# LineOut_Headphone_Rev2.net
KiCad netlist of a schematic drawn in EAGLE
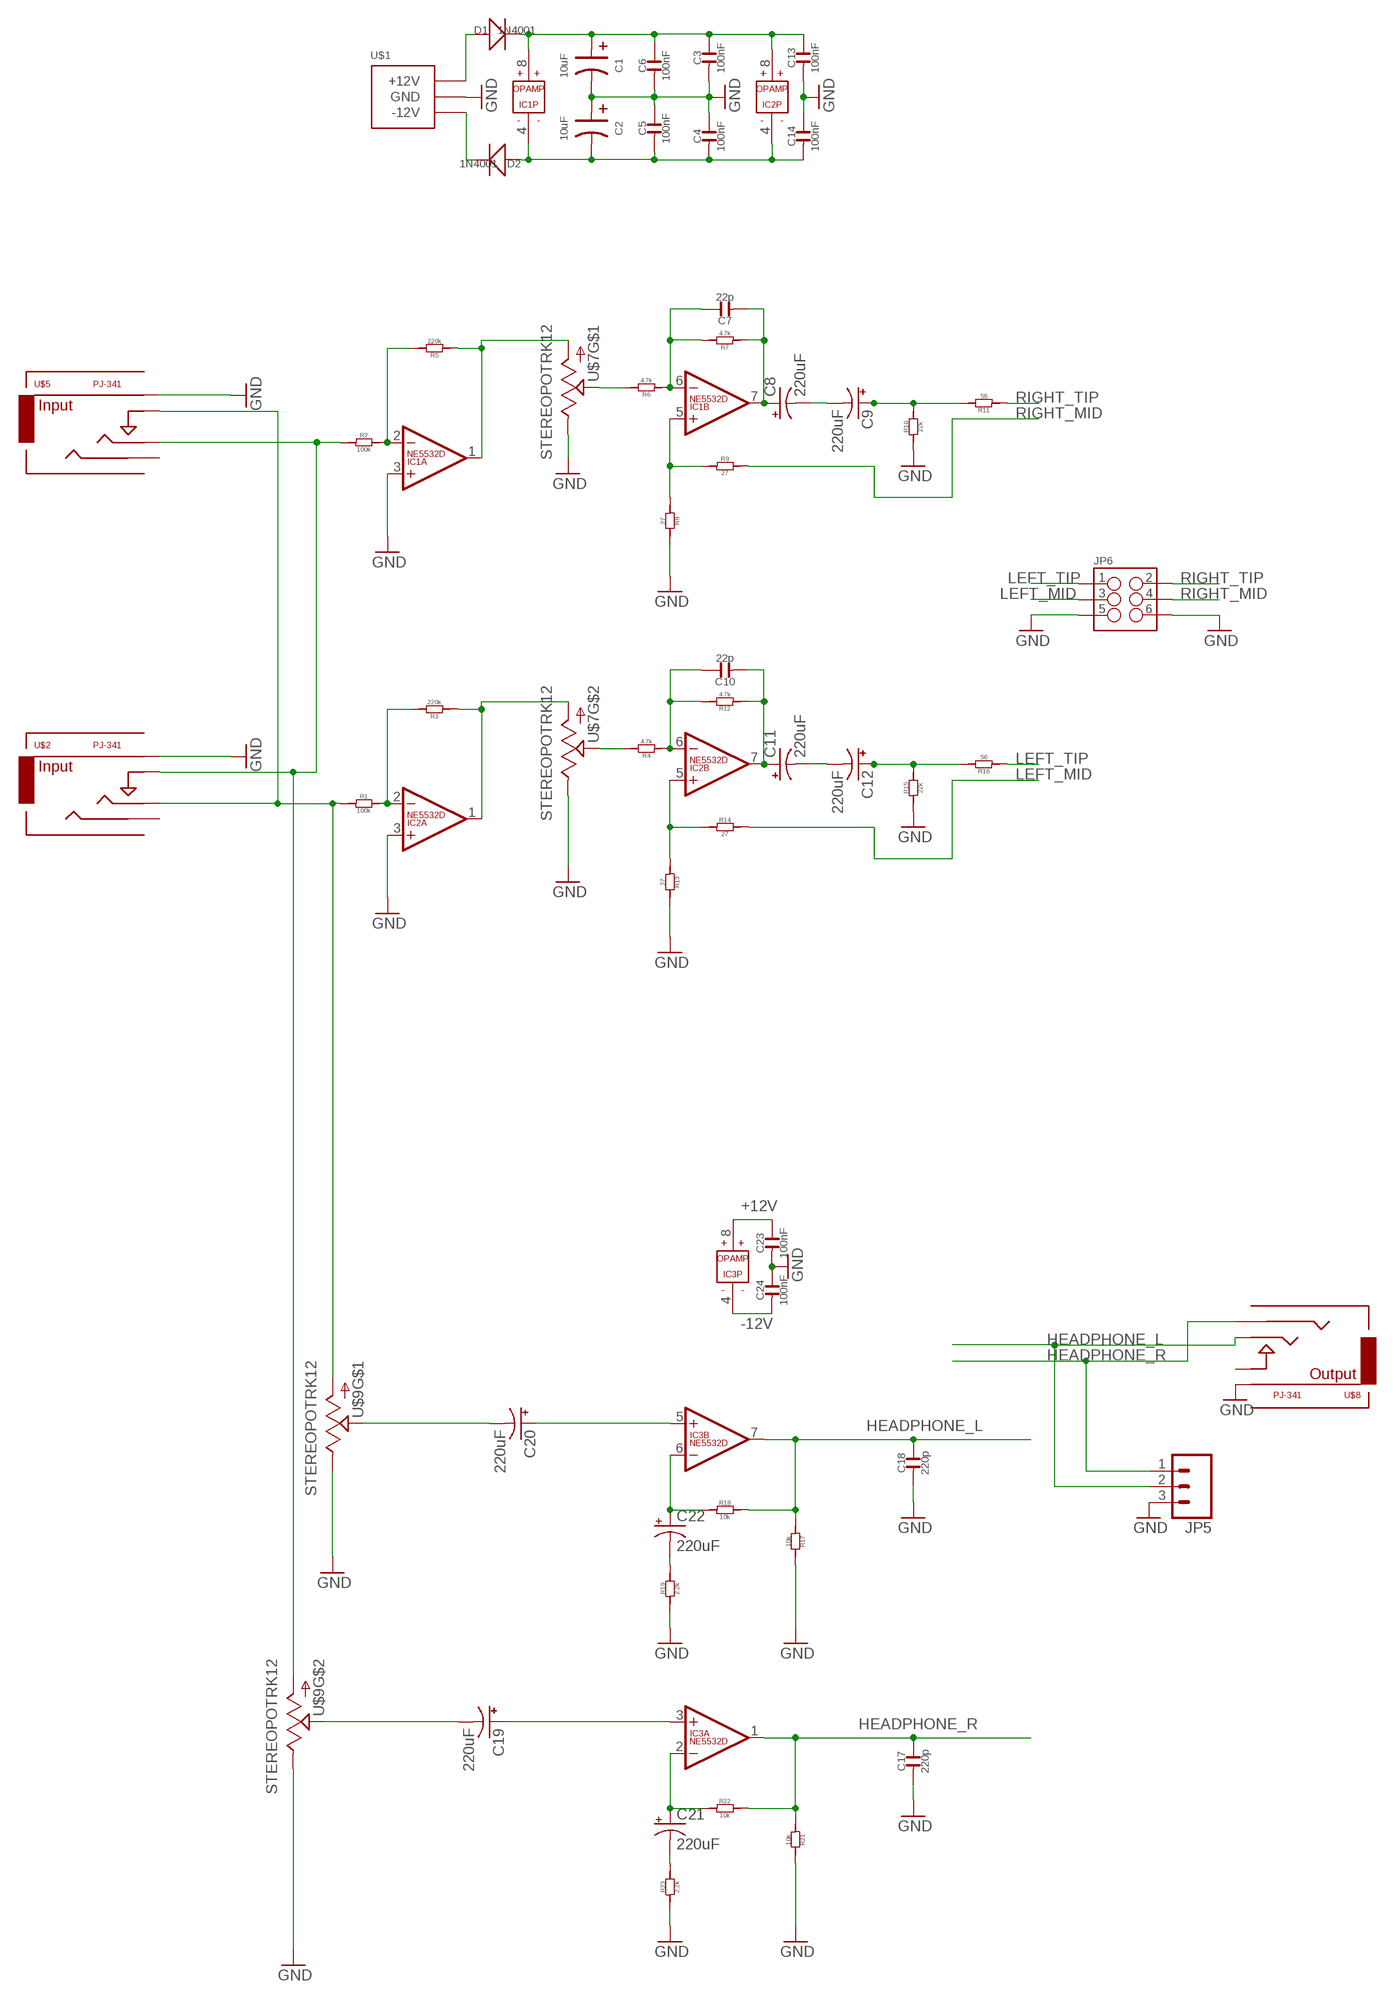
[diagram p0: schematic, sheet 1]

(export (version "E")
  (design (tool "Eeschema 10.0.6"))
  (components
    (comp (ref "C1")
      (value "10uF")
      (footprint "eagle-import:CASE-A_3216")
      (libsource (lib "eagle-import") (part "C-POLAR-A"))
    )
    (comp (ref "C2")
      (value "10uF")
      (footprint "eagle-import:CASE-A_3216")
      (libsource (lib "eagle-import") (part "C-POLAR-A"))
    )
    (comp (ref "C3")
      (value "100nF")
      (footprint "eagle-import:C0603")
      (libsource (lib "eagle-import") (part "C-0603"))
    )
    (comp (ref "C4")
      (value "100nF")
      (footprint "eagle-import:C0603")
      (libsource (lib "eagle-import") (part "C-0603"))
    )
    (comp (ref "C5")
      (value "100nF")
      (footprint "eagle-import:C0603")
      (libsource (lib "eagle-import") (part "C-0603"))
    )
    (comp (ref "C6")
      (value "100nF")
      (footprint "eagle-import:C0603")
      (libsource (lib "eagle-import") (part "C-0603"))
    )
    (comp (ref "C7")
      (value "22p")
      (footprint "eagle-import:C0603")
      (libsource (lib "eagle-import") (part "C-0603"))
    )
    (comp (ref "C8")
      (value "220uF")
      (footprint "eagle-import:153CLV-0505")
      (libsource (lib "eagle-import") (part "CPOL-US153CLV-0505"))
    )
    (comp (ref "C9")
      (value "220uF")
      (footprint "eagle-import:153CLV-0505")
      (libsource (lib "eagle-import") (part "CPOL-US153CLV-0505"))
    )
    (comp (ref "C10")
      (value "22p")
      (footprint "eagle-import:C0603")
      (libsource (lib "eagle-import") (part "C-0603"))
    )
    (comp (ref "C11")
      (value "220uF")
      (footprint "eagle-import:153CLV-0505")
      (libsource (lib "eagle-import") (part "CPOL-US153CLV-0505"))
    )
    (comp (ref "C12")
      (value "220uF")
      (footprint "eagle-import:153CLV-0505")
      (libsource (lib "eagle-import") (part "CPOL-US153CLV-0505"))
    )
    (comp (ref "C13")
      (value "100nF")
      (footprint "eagle-import:C0603")
      (libsource (lib "eagle-import") (part "C-0603"))
    )
    (comp (ref "C14")
      (value "100nF")
      (footprint "eagle-import:C0603")
      (libsource (lib "eagle-import") (part "C-0603"))
    )
    (comp (ref "C17")
      (value "220p")
      (footprint "eagle-import:C0603")
      (libsource (lib "eagle-import") (part "C-0603"))
    )
    (comp (ref "C18")
      (value "220p")
      (footprint "eagle-import:C0603")
      (libsource (lib "eagle-import") (part "C-0603"))
    )
    (comp (ref "C19")
      (value "220uF")
      (footprint "eagle-import:153CLV-0505")
      (libsource (lib "eagle-import") (part "CPOL-US153CLV-0505"))
    )
    (comp (ref "C20")
      (value "220uF")
      (footprint "eagle-import:153CLV-0505")
      (libsource (lib "eagle-import") (part "CPOL-US153CLV-0505"))
    )
    (comp (ref "C21")
      (value "220uF")
      (footprint "eagle-import:153CLV-0505")
      (libsource (lib "eagle-import") (part "CPOL-US153CLV-0505"))
    )
    (comp (ref "C22")
      (value "220uF")
      (footprint "eagle-import:153CLV-0505")
      (libsource (lib "eagle-import") (part "CPOL-US153CLV-0505"))
    )
    (comp (ref "C23")
      (value "100nF")
      (footprint "eagle-import:C0603")
      (libsource (lib "eagle-import") (part "C-0603"))
    )
    (comp (ref "C24")
      (value "100nF")
      (footprint "eagle-import:C0603")
      (libsource (lib "eagle-import") (part "C-0603"))
    )
    (comp (ref "D1")
      (value "1N4001")
      (footprint "eagle-import:SOD123")
      (libsource (lib "eagle-import") (part "D-SOD-123"))
    )
    (comp (ref "D2")
      (value "1N4001")
      (footprint "eagle-import:SOD123")
      (libsource (lib "eagle-import") (part "D-SOD-123"))
    )
    (comp (ref "IC1")
      (value "NE5532D")
      (footprint "eagle-import:SO08")
      (libsource (lib "eagle-import") (part "NE5532D"))
    )
    (comp (ref "IC2")
      (value "NE5532D")
      (footprint "eagle-import:SO08")
      (libsource (lib "eagle-import") (part "NE5532D"))
    )
    (comp (ref "IC3")
      (value "NE5532D")
      (footprint "eagle-import:SO08")
      (libsource (lib "eagle-import") (part "NE5532D"))
    )
    (comp (ref "JP5")
      (value "M03PTH")
      (footprint "eagle-import:1X03")
      (libsource (lib "eagle-import") (part "M03PTH"))
    )
    (comp (ref "JP6")
      (value "M03X2")
      (footprint "eagle-import:2X3-SHROUDED")
      (libsource (lib "eagle-import") (part "M03X2"))
    )
    (comp (ref "R1")
      (value "100k")
      (footprint "eagle-import:R0603")
      (libsource (lib "eagle-import") (part "R-0603"))
    )
    (comp (ref "R2")
      (value "100k")
      (footprint "eagle-import:R0603")
      (libsource (lib "eagle-import") (part "R-0603"))
    )
    (comp (ref "R3")
      (value "220k")
      (footprint "eagle-import:R0603")
      (libsource (lib "eagle-import") (part "R-0603"))
    )
    (comp (ref "R4")
      (value "4.7k")
      (footprint "eagle-import:R0603")
      (libsource (lib "eagle-import") (part "R-0603"))
    )
    (comp (ref "R5")
      (value "220k")
      (footprint "eagle-import:R0603")
      (libsource (lib "eagle-import") (part "R-0603"))
    )
    (comp (ref "R6")
      (value "4.7k")
      (footprint "eagle-import:R0603")
      (libsource (lib "eagle-import") (part "R-0603"))
    )
    (comp (ref "R7")
      (value "4.7k")
      (footprint "eagle-import:R0603")
      (libsource (lib "eagle-import") (part "R-0603"))
    )
    (comp (ref "R8")
      (value "27")
      (footprint "eagle-import:R0603")
      (libsource (lib "eagle-import") (part "R-0603"))
    )
    (comp (ref "R9")
      (value "27")
      (footprint "eagle-import:R0603")
      (libsource (lib "eagle-import") (part "R-0603"))
    )
    (comp (ref "R10")
      (value "22k")
      (footprint "eagle-import:R0603")
      (libsource (lib "eagle-import") (part "R-0603"))
    )
    (comp (ref "R11")
      (value "56")
      (footprint "eagle-import:R0603")
      (libsource (lib "eagle-import") (part "R-0603"))
    )
    (comp (ref "R12")
      (value "4.7k")
      (footprint "eagle-import:R0603")
      (libsource (lib "eagle-import") (part "R-0603"))
    )
    (comp (ref "R13")
      (value "27")
      (footprint "eagle-import:R0603")
      (libsource (lib "eagle-import") (part "R-0603"))
    )
    (comp (ref "R14")
      (value "27")
      (footprint "eagle-import:R0603")
      (libsource (lib "eagle-import") (part "R-0603"))
    )
    (comp (ref "R15")
      (value "22k")
      (footprint "eagle-import:R0603")
      (libsource (lib "eagle-import") (part "R-0603"))
    )
    (comp (ref "R16")
      (value "56")
      (footprint "eagle-import:R0603")
      (libsource (lib "eagle-import") (part "R-0603"))
    )
    (comp (ref "R17")
      (value "10k")
      (footprint "eagle-import:R0603")
      (libsource (lib "eagle-import") (part "R-0603"))
    )
    (comp (ref "R18")
      (value "10k")
      (footprint "eagle-import:R0603")
      (libsource (lib "eagle-import") (part "R-0603"))
    )
    (comp (ref "R19")
      (value "2.2k")
      (footprint "eagle-import:R0603")
      (libsource (lib "eagle-import") (part "R-0603"))
    )
    (comp (ref "R21")
      (value "10k")
      (footprint "eagle-import:R0603")
      (libsource (lib "eagle-import") (part "R-0603"))
    )
    (comp (ref "R22")
      (value "10k")
      (footprint "eagle-import:R0603")
      (libsource (lib "eagle-import") (part "R-0603"))
    )
    (comp (ref "R23")
      (value "2.2k")
      (footprint "eagle-import:R0603")
      (libsource (lib "eagle-import") (part "R-0603"))
    )
    (comp (ref "U$1")
      (value "POWER_SIMPLE10")
      (footprint "eagle-import:POWER_10")
      (libsource (lib "eagle-import") (part "POWER_SIMPLE10"))
    )
    (comp (ref "U$2")
      (value "PJ-341")
      (footprint "eagle-import:3.5MM-JACK-SWITCH-13MM-INPUT")
      (libsource (lib "eagle-import") (part "AUDIO-JACKINPUT"))
    )
    (comp (ref "U$5")
      (value "PJ-341")
      (footprint "eagle-import:3.5MM-JACK-SWITCH-13MM-INPUT")
      (libsource (lib "eagle-import") (part "AUDIO-JACKINPUT"))
    )
    (comp (ref "U$7")
      (value "STEREOPOTRK12")
      (footprint "eagle-import:RK12")
      (libsource (lib "eagle-import") (part "STEREOPOTRK12"))
    )
    (comp (ref "U$8")
      (value "PJ-341")
      (footprint "eagle-import:3.5MM-JACK-SWITCH-13MM-OUTPUT")
      (libsource (lib "eagle-import") (part "AUDIO-JACKOUTPUT"))
    )
    (comp (ref "U$9")
      (value "STEREOPOTRK12")
      (footprint "eagle-import:RK12")
      (libsource (lib "eagle-import") (part "STEREOPOTRK12"))
    )
  )
  (nets
    (net (code "1") (name "/+12V") (class "Default")
      (node (ref "C1") (pin "+") (pinfunction "1_+") (pintype "bidirectional"))
      (node (ref "C13") (pin "2") (pinfunction "2_2") (pintype "bidirectional"))
      (node (ref "C23") (pin "2") (pinfunction "2_2") (pintype "bidirectional"))
      (node (ref "C3") (pin "2") (pinfunction "2_2") (pintype "bidirectional"))
      (node (ref "C6") (pin "2") (pinfunction "2_2") (pintype "bidirectional"))
      (node (ref "D1") (pin "-") (pinfunction "-_-") (pintype "passive"))
      (node (ref "IC1") (pin "8") (pinfunction "V+_8") (pintype "power_in"))
      (node (ref "IC2") (pin "8") (pinfunction "V+_8") (pintype "power_in"))
      (node (ref "IC3") (pin "8") (pinfunction "V+_8") (pintype "power_in"))
    )
    (net (code "2") (name "/-12V") (class "Default")
      (node (ref "C14") (pin "1") (pinfunction "1_1") (pintype "bidirectional"))
      (node (ref "C2") (pin "-") (pinfunction "2_-") (pintype "bidirectional"))
      (node (ref "C24") (pin "1") (pinfunction "1_1") (pintype "bidirectional"))
      (node (ref "C4") (pin "1") (pinfunction "1_1") (pintype "bidirectional"))
      (node (ref "C5") (pin "1") (pinfunction "1_1") (pintype "bidirectional"))
      (node (ref "D2") (pin "+") (pinfunction "+_+") (pintype "passive"))
      (node (ref "IC1") (pin "4") (pinfunction "V-_4") (pintype "power_in"))
      (node (ref "IC2") (pin "4") (pinfunction "V-_4") (pintype "power_in"))
      (node (ref "IC3") (pin "4") (pinfunction "V-_4") (pintype "power_in"))
    )
    (net (code "3") (name "/HEADPHONE_L") (class "Default")
      (node (ref "C18") (pin "2") (pinfunction "2_2") (pintype "bidirectional"))
      (node (ref "IC3") (pin "7") (pinfunction "OUT_7") (pintype "output"))
      (node (ref "JP5") (pin "2") (pinfunction "2_2") (pintype "passive"))
      (node (ref "R17") (pin "1") (pinfunction "1_1") (pintype "bidirectional"))
      (node (ref "R18") (pin "2") (pinfunction "2_2") (pintype "bidirectional"))
      (node (ref "U$8") (pin "TIP@3") (pinfunction "TIP_TIP@3") (pintype "bidirectional"))
    )
    (net (code "4") (name "/HEADPHONE_R") (class "Default")
      (node (ref "C17") (pin "2") (pinfunction "2_2") (pintype "bidirectional"))
      (node (ref "IC3") (pin "1") (pinfunction "OUT_1") (pintype "output"))
      (node (ref "JP5") (pin "1") (pinfunction "1_1") (pintype "passive"))
      (node (ref "R21") (pin "1") (pinfunction "1_1") (pintype "bidirectional"))
      (node (ref "R22") (pin "2") (pinfunction "2_2") (pintype "bidirectional"))
      (node (ref "U$8") (pin "SECOND@3") (pinfunction "SECOND_SECOND@3") (pintype "bidirectional"))
    )
    (net (code "5") (name "/LEFT_MID") (class "Default")
      (node (ref "JP6") (pin "3") (pinfunction "3_3") (pintype "bidirectional"))
      (node (ref "R14") (pin "2") (pinfunction "2_2") (pintype "bidirectional"))
    )
    (net (code "6") (name "/LEFT_TIP") (class "Default")
      (node (ref "JP6") (pin "1") (pinfunction "1_1") (pintype "bidirectional"))
      (node (ref "R16") (pin "1") (pinfunction "1_1") (pintype "bidirectional"))
    )
    (net (code "7") (name "/RIGHT_MID") (class "Default")
      (node (ref "JP6") (pin "4") (pinfunction "4_4") (pintype "bidirectional"))
      (node (ref "R9") (pin "2") (pinfunction "2_2") (pintype "bidirectional"))
    )
    (net (code "8") (name "/RIGHT_TIP") (class "Default")
      (node (ref "JP6") (pin "2") (pinfunction "2_2") (pintype "bidirectional"))
      (node (ref "R11") (pin "1") (pinfunction "1_1") (pintype "bidirectional"))
    )
    (net (code "9") (name "GND") (class "Default")
      (node (ref "C1") (pin "-") (pinfunction "2_-") (pintype "bidirectional"))
      (node (ref "C13") (pin "1") (pinfunction "1_1") (pintype "bidirectional"))
      (node (ref "C14") (pin "2") (pinfunction "2_2") (pintype "bidirectional"))
      (node (ref "C17") (pin "1") (pinfunction "1_1") (pintype "bidirectional"))
      (node (ref "C18") (pin "1") (pinfunction "1_1") (pintype "bidirectional"))
      (node (ref "C2") (pin "+") (pinfunction "1_+") (pintype "bidirectional"))
      (node (ref "C23") (pin "1") (pinfunction "1_1") (pintype "bidirectional"))
      (node (ref "C24") (pin "2") (pinfunction "2_2") (pintype "bidirectional"))
      (node (ref "C3") (pin "1") (pinfunction "1_1") (pintype "bidirectional"))
      (node (ref "C4") (pin "2") (pinfunction "2_2") (pintype "bidirectional"))
      (node (ref "C5") (pin "2") (pinfunction "2_2") (pintype "bidirectional"))
      (node (ref "C6") (pin "1") (pinfunction "1_1") (pintype "bidirectional"))
      (node (ref "IC1") (pin "3") (pinfunction "+IN_3") (pintype "input"))
      (node (ref "IC2") (pin "3") (pinfunction "+IN_3") (pintype "input"))
      (node (ref "JP5") (pin "3") (pinfunction "3_3") (pintype "passive"))
      (node (ref "JP6") (pin "5") (pinfunction "5_5") (pintype "bidirectional"))
      (node (ref "JP6") (pin "6") (pinfunction "6_6") (pintype "bidirectional"))
      (node (ref "R10") (pin "1") (pinfunction "1_1") (pintype "bidirectional"))
      (node (ref "R13") (pin "2") (pinfunction "2_2") (pintype "bidirectional"))
      (node (ref "R15") (pin "1") (pinfunction "1_1") (pintype "bidirectional"))
      (node (ref "R17") (pin "2") (pinfunction "2_2") (pintype "bidirectional"))
      (node (ref "R19") (pin "1") (pinfunction "1_1") (pintype "bidirectional"))
      (node (ref "R21") (pin "2") (pinfunction "2_2") (pintype "bidirectional"))
      (node (ref "R23") (pin "1") (pinfunction "1_1") (pintype "bidirectional"))
      (node (ref "R8") (pin "2") (pinfunction "2_2") (pintype "bidirectional"))
      (node (ref "U$1") (pin "3") (pinfunction "GND_3") (pintype "bidirectional"))
      (node (ref "U$1") (pin "4") (pinfunction "GND_4") (pintype "bidirectional"))
      (node (ref "U$1") (pin "5") (pinfunction "GND_5") (pintype "bidirectional"))
      (node (ref "U$1") (pin "6") (pinfunction "GND_6") (pintype "bidirectional"))
      (node (ref "U$1") (pin "7") (pinfunction "GND_7") (pintype "bidirectional"))
      (node (ref "U$1") (pin "8") (pinfunction "GND_8") (pintype "bidirectional"))
      (node (ref "U$2") (pin "RING@3") (pinfunction "RING_RING@3") (pintype "bidirectional"))
      (node (ref "U$5") (pin "RING@3") (pinfunction "RING_RING@3") (pintype "bidirectional"))
      (node (ref "U$7") (pin "R1_1") (pinfunction "E_R1_1") (pintype "passive"))
      (node (ref "U$7") (pin "R2_1") (pinfunction "E_R2_1") (pintype "passive"))
      (node (ref "U$8") (pin "RING@3") (pinfunction "RING_RING@3") (pintype "bidirectional"))
      (node (ref "U$9") (pin "R1_1") (pinfunction "E_R1_1") (pintype "passive"))
      (node (ref "U$9") (pin "R2_1") (pinfunction "E_R2_1") (pintype "passive"))
    )
    (net (code "10") (name "Net-(C8-Pad-)") (class "Default")
      (node (ref "C8") (pin "-") (pinfunction "-_-") (pintype "passive"))
      (node (ref "C9") (pin "-") (pinfunction "-_-") (pintype "passive"))
    )
    (net (code "11") (name "Net-(C9-Pad+)") (class "Default")
      (node (ref "C9") (pin "+") (pinfunction "+_+") (pintype "passive"))
      (node (ref "R10") (pin "2") (pinfunction "2_2") (pintype "bidirectional"))
      (node (ref "R11") (pin "2") (pinfunction "2_2") (pintype "bidirectional"))
    )
    (net (code "12") (name "Net-(C11-Pad-)") (class "Default")
      (node (ref "C11") (pin "-") (pinfunction "-_-") (pintype "passive"))
      (node (ref "C12") (pin "-") (pinfunction "-_-") (pintype "passive"))
    )
    (net (code "13") (name "Net-(C12-Pad+)") (class "Default")
      (node (ref "C12") (pin "+") (pinfunction "+_+") (pintype "passive"))
      (node (ref "R15") (pin "2") (pinfunction "2_2") (pintype "bidirectional"))
      (node (ref "R16") (pin "2") (pinfunction "2_2") (pintype "bidirectional"))
    )
    (net (code "14") (name "Net-(C21-Pad-)") (class "Default")
      (node (ref "C21") (pin "-") (pinfunction "-_-") (pintype "passive"))
      (node (ref "R23") (pin "2") (pinfunction "2_2") (pintype "bidirectional"))
    )
    (net (code "15") (name "Net-(C22-Pad-)") (class "Default")
      (node (ref "C22") (pin "-") (pinfunction "-_-") (pintype "passive"))
      (node (ref "R19") (pin "2") (pinfunction "2_2") (pintype "bidirectional"))
    )
    (net (code "16") (name "Net-(D1-Pad+)") (class "Default")
      (node (ref "D1") (pin "+") (pinfunction "+_+") (pintype "passive"))
      (node (ref "U$1") (pin "10") (pinfunction "+12V_10") (pintype "bidirectional"))
      (node (ref "U$1") (pin "9") (pinfunction "+12V_9") (pintype "bidirectional"))
    )
    (net (code "17") (name "Net-(D2-Pad-)") (class "Default")
      (node (ref "D2") (pin "-") (pinfunction "-_-") (pintype "passive"))
      (node (ref "U$1") (pin "1") (pinfunction "-12V_1") (pintype "bidirectional"))
      (node (ref "U$1") (pin "2") (pinfunction "-12V_2") (pintype "bidirectional"))
    )
    (net (code "18") (name "Net-(IC1A--IN)") (class "Default")
      (node (ref "IC1") (pin "2") (pinfunction "-IN_2") (pintype "input"))
      (node (ref "R2") (pin "2") (pinfunction "2_2") (pintype "bidirectional"))
      (node (ref "R5") (pin "2") (pinfunction "2_2") (pintype "bidirectional"))
    )
    (net (code "19") (name "Net-(IC1A-OUT)") (class "Default")
      (node (ref "IC1") (pin "1") (pinfunction "OUT_1") (pintype "output"))
      (node (ref "R5") (pin "1") (pinfunction "1_1") (pintype "bidirectional"))
      (node (ref "U$7") (pin "R1_3") (pinfunction "A_R1_3") (pintype "passive"))
    )
    (net (code "20") (name "Net-(IC1B-+IN)") (class "Default")
      (node (ref "IC1") (pin "5") (pinfunction "+IN_5") (pintype "input"))
      (node (ref "R8") (pin "1") (pinfunction "1_1") (pintype "bidirectional"))
      (node (ref "R9") (pin "1") (pinfunction "1_1") (pintype "bidirectional"))
    )
    (net (code "21") (name "Net-(IC1B--IN)") (class "Default")
      (node (ref "C7") (pin "2") (pinfunction "2_2") (pintype "bidirectional"))
      (node (ref "IC1") (pin "6") (pinfunction "-IN_6") (pintype "input"))
      (node (ref "R6") (pin "1") (pinfunction "1_1") (pintype "bidirectional"))
      (node (ref "R7") (pin "2") (pinfunction "2_2") (pintype "bidirectional"))
    )
    (net (code "22") (name "Net-(IC1B-OUT)") (class "Default")
      (node (ref "C7") (pin "1") (pinfunction "1_1") (pintype "bidirectional"))
      (node (ref "C8") (pin "+") (pinfunction "+_+") (pintype "passive"))
      (node (ref "IC1") (pin "7") (pinfunction "OUT_7") (pintype "output"))
      (node (ref "R7") (pin "1") (pinfunction "1_1") (pintype "bidirectional"))
    )
    (net (code "23") (name "Net-(IC2A--IN)") (class "Default")
      (node (ref "IC2") (pin "2") (pinfunction "-IN_2") (pintype "input"))
      (node (ref "R1") (pin "2") (pinfunction "2_2") (pintype "bidirectional"))
      (node (ref "R3") (pin "2") (pinfunction "2_2") (pintype "bidirectional"))
    )
    (net (code "24") (name "Net-(IC2A-OUT)") (class "Default")
      (node (ref "IC2") (pin "1") (pinfunction "OUT_1") (pintype "output"))
      (node (ref "R3") (pin "1") (pinfunction "1_1") (pintype "bidirectional"))
      (node (ref "U$7") (pin "R2_3") (pinfunction "A_R2_3") (pintype "passive"))
    )
    (net (code "25") (name "Net-(IC2B-+IN)") (class "Default")
      (node (ref "IC2") (pin "5") (pinfunction "+IN_5") (pintype "input"))
      (node (ref "R13") (pin "1") (pinfunction "1_1") (pintype "bidirectional"))
      (node (ref "R14") (pin "1") (pinfunction "1_1") (pintype "bidirectional"))
    )
    (net (code "26") (name "Net-(IC2B--IN)") (class "Default")
      (node (ref "C10") (pin "2") (pinfunction "2_2") (pintype "bidirectional"))
      (node (ref "IC2") (pin "6") (pinfunction "-IN_6") (pintype "input"))
      (node (ref "R12") (pin "2") (pinfunction "2_2") (pintype "bidirectional"))
      (node (ref "R4") (pin "1") (pinfunction "1_1") (pintype "bidirectional"))
    )
    (net (code "27") (name "Net-(IC2B-OUT)") (class "Default")
      (node (ref "C10") (pin "1") (pinfunction "1_1") (pintype "bidirectional"))
      (node (ref "C11") (pin "+") (pinfunction "+_+") (pintype "passive"))
      (node (ref "IC2") (pin "7") (pinfunction "OUT_7") (pintype "output"))
      (node (ref "R12") (pin "1") (pinfunction "1_1") (pintype "bidirectional"))
    )
    (net (code "28") (name "Net-(IC3A-+IN)") (class "Default")
      (node (ref "C19") (pin "+") (pinfunction "+_+") (pintype "passive"))
      (node (ref "IC3") (pin "3") (pinfunction "+IN_3") (pintype "input"))
    )
    (net (code "29") (name "Net-(IC3A--IN)") (class "Default")
      (node (ref "C21") (pin "+") (pinfunction "+_+") (pintype "passive"))
      (node (ref "IC3") (pin "2") (pinfunction "-IN_2") (pintype "input"))
      (node (ref "R22") (pin "1") (pinfunction "1_1") (pintype "bidirectional"))
    )
    (net (code "30") (name "Net-(IC3B-+IN)") (class "Default")
      (node (ref "C20") (pin "+") (pinfunction "+_+") (pintype "passive"))
      (node (ref "IC3") (pin "5") (pinfunction "+IN_5") (pintype "input"))
    )
    (net (code "31") (name "Net-(IC3B--IN)") (class "Default")
      (node (ref "C22") (pin "+") (pinfunction "+_+") (pintype "passive"))
      (node (ref "IC3") (pin "6") (pinfunction "-IN_6") (pintype "input"))
      (node (ref "R18") (pin "1") (pinfunction "1_1") (pintype "bidirectional"))
    )
    (net (code "32") (name "Net-(U$2-SWITCH)") (class "Default")
      (node (ref "R2") (pin "1") (pinfunction "1_1") (pintype "bidirectional"))
      (node (ref "U$2") (pin "SWITCH@3") (pinfunction "SWITCH_SWITCH@3") (pintype "bidirectional"))
      (node (ref "U$5") (pin "TIP@3") (pinfunction "TIP_TIP@3") (pintype "bidirectional"))
      (node (ref "U$9") (pin "R2_3") (pinfunction "A_R2_3") (pintype "passive"))
    )
    (net (code "33") (name "Net-(U$2-TIP)") (class "Default")
      (node (ref "R1") (pin "1") (pinfunction "1_1") (pintype "bidirectional"))
      (node (ref "U$2") (pin "TIP@3") (pinfunction "TIP_TIP@3") (pintype "bidirectional"))
      (node (ref "U$5") (pin "SWITCH@3") (pinfunction "SWITCH_SWITCH@3") (pintype "bidirectional"))
      (node (ref "U$9") (pin "R1_3") (pinfunction "A_R1_3") (pintype "passive"))
    )
    (net (code "34") (name "Net-(U$7A-S)") (class "Default")
      (node (ref "R6") (pin "2") (pinfunction "2_2") (pintype "bidirectional"))
      (node (ref "U$7") (pin "R1_2") (pinfunction "S_R1_2") (pintype "passive"))
    )
    (net (code "35") (name "Net-(U$7B-S)") (class "Default")
      (node (ref "R4") (pin "2") (pinfunction "2_2") (pintype "bidirectional"))
      (node (ref "U$7") (pin "R2_2") (pinfunction "S_R2_2") (pintype "passive"))
    )
    (net (code "36") (name "Net-(U$9A-S)") (class "Default")
      (node (ref "C20") (pin "-") (pinfunction "-_-") (pintype "passive"))
      (node (ref "U$9") (pin "R1_2") (pinfunction "S_R1_2") (pintype "passive"))
    )
    (net (code "37") (name "Net-(U$9B-S)") (class "Default")
      (node (ref "C19") (pin "-") (pinfunction "-_-") (pintype "passive"))
      (node (ref "U$9") (pin "R2_2") (pinfunction "S_R2_2") (pintype "passive"))
    )
    (net (code "38") (name "unconnected-(U$2-SECOND-PadSECOND@3)") (class "Default")
      (node (ref "U$2") (pin "SECOND@3") (pinfunction "SECOND_SECOND@3") (pintype "bidirectional"))
    )
    (net (code "39") (name "unconnected-(U$5-SECOND-PadSECOND@3)") (class "Default")
      (node (ref "U$5") (pin "SECOND@3") (pinfunction "SECOND_SECOND@3") (pintype "bidirectional"))
    )
    (net (code "40") (name "unconnected-(U$8-SWITCH-PadSWITCH@3)") (class "Default")
      (node (ref "U$8") (pin "SWITCH@3") (pinfunction "SWITCH_SWITCH@3") (pintype "bidirectional"))
    )
  )
)
